# Battlebot_Main.net
KiCad netlist of a schematic drawn in Altium Designer
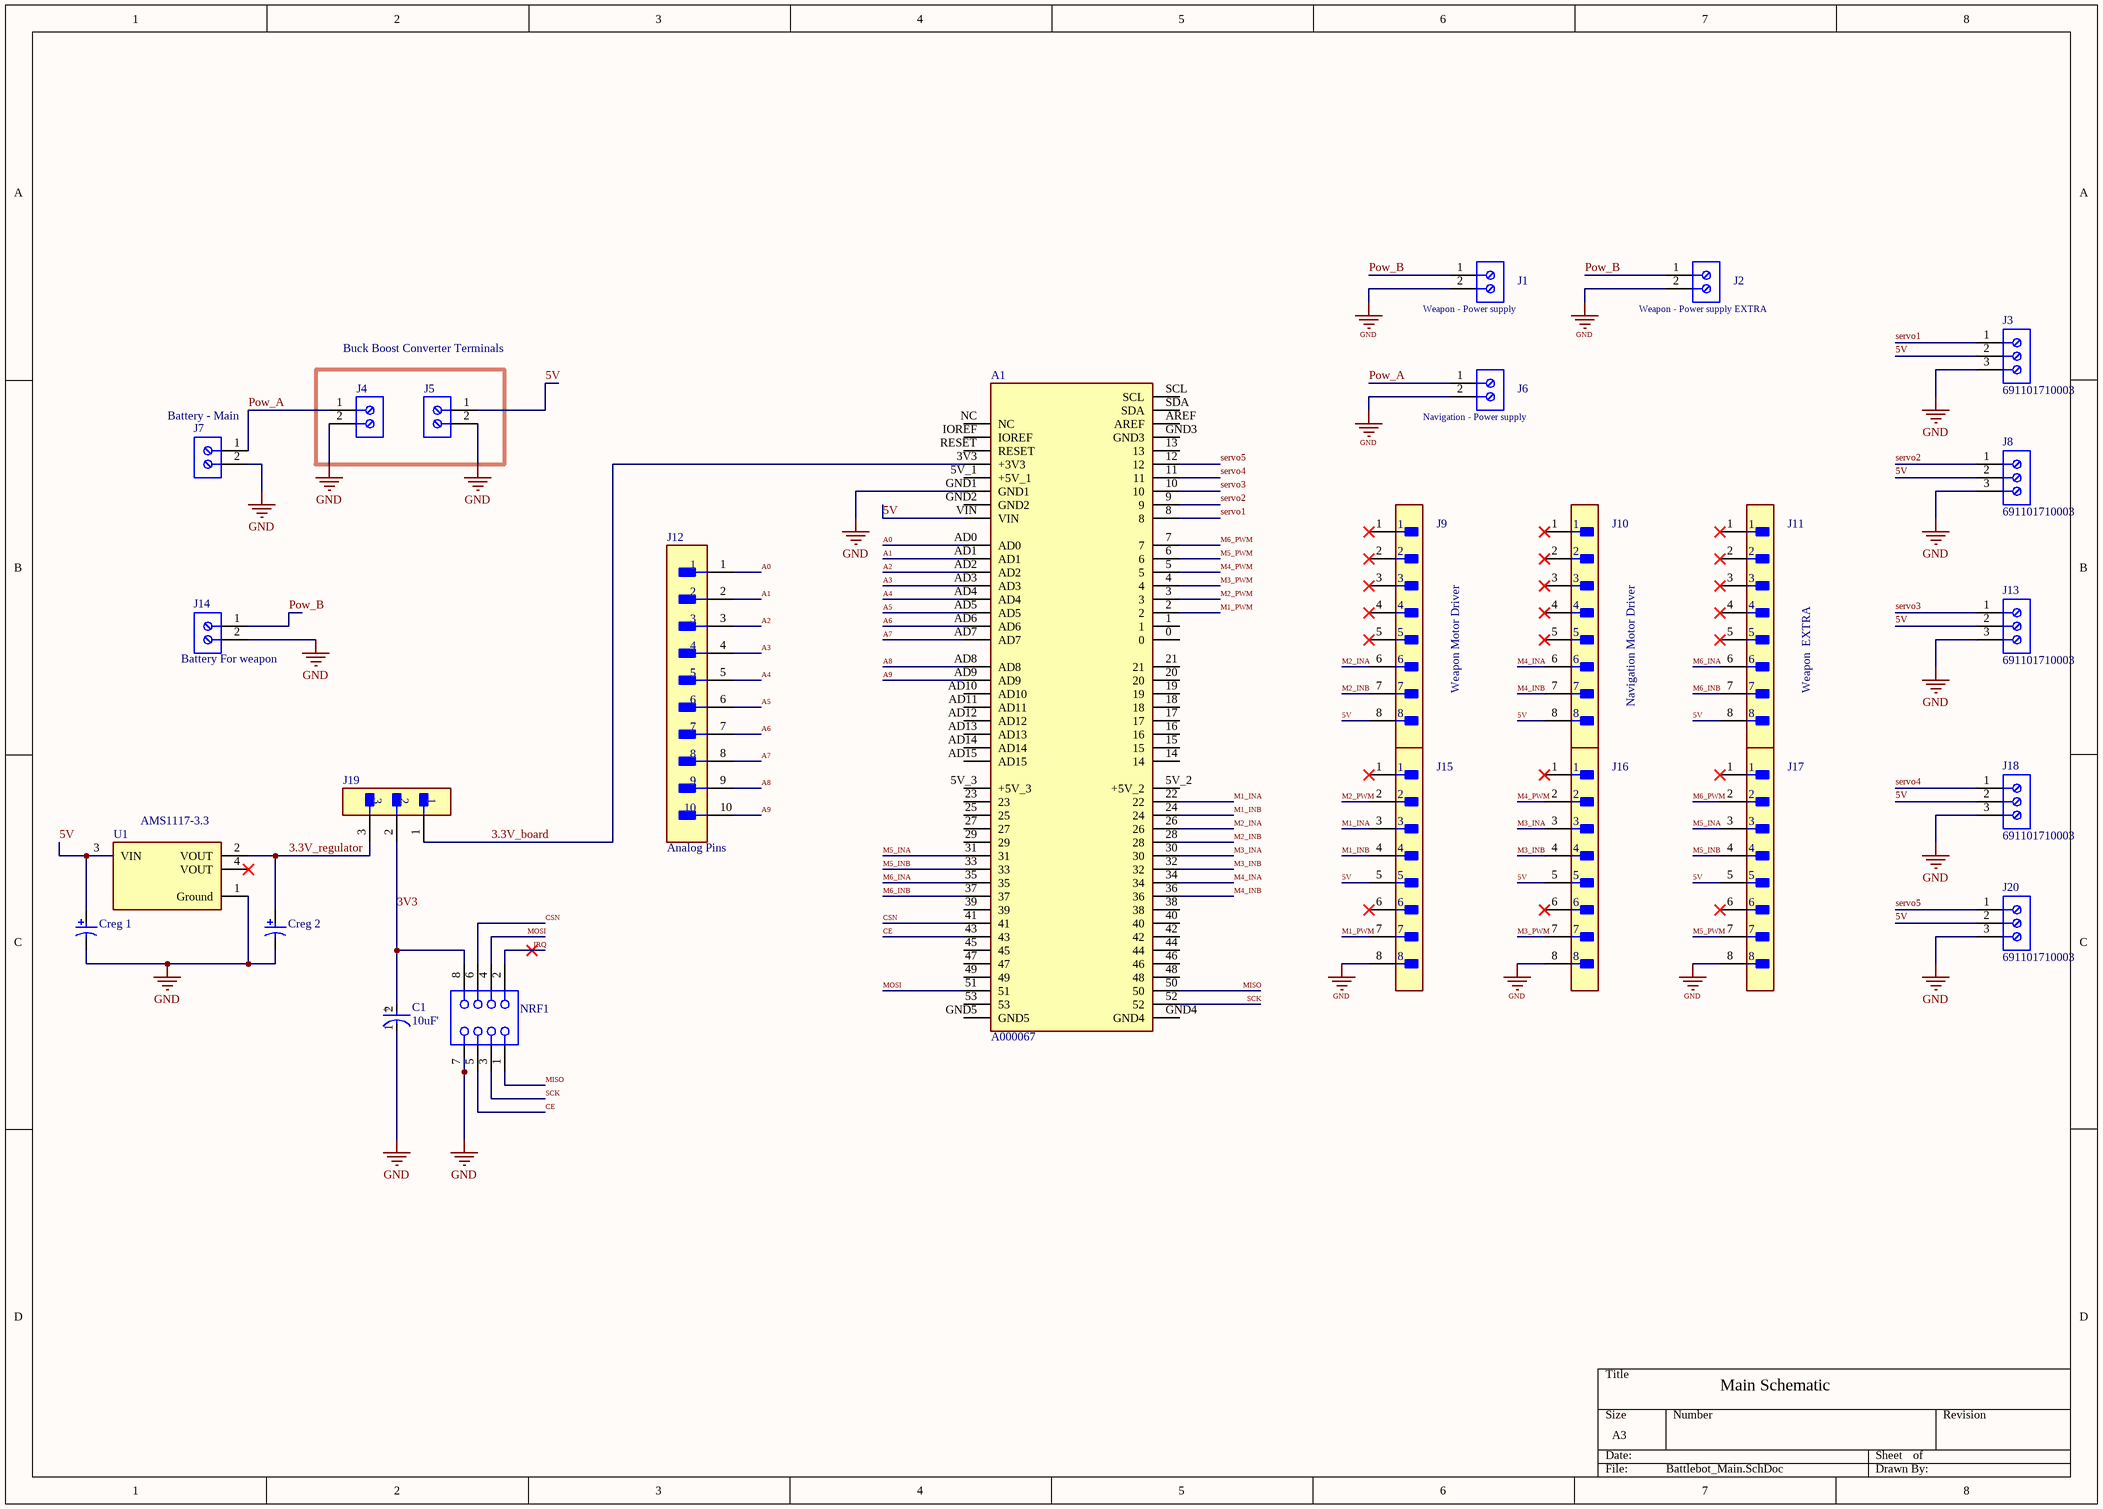
[diagram p0: Battlebot_Main.SchDoc]

(export (version "E")
  (design (tool "Eeschema 10.0.6"))
  (components
    (comp (ref "A1")
      (value "A000067")
      (footprint "ARDUINO_A000067")
      (fields (field (name "MF") "Arduino"))
      (libsource (lib "Schlib1") (part "A000067"))
    )
    (comp (ref "C1")
      (value "10uF'")
      (footprint "FP-RAD-TH-D_5_0_5-L_11_1-MFG")
      (description "Aluminum Electrolytic Capacitors (Radial Lead Type) AEC-Q200 Qualified 47uF ±20% 35V")
      (fields (field (name "VOLTAGE") "35V") (field (name "TOLERANCE") "20%"))
      (libsource (lib "Altium Content Vault") (part "a00bbbee19879c290e62620ae7e47b1"))
    )
    (comp (ref "Creg 1")
      (value "ECA1HM100")
      (footprint "CAPPR55-200-1100X500X1200")
      (description "Aluminum Electrolytic Capacitor, 10 uF, +/- 20%, 50 V, -40 to 85 degC, 2-Pin THD, RoHS, Bulk")
      (fields (field (name "MANUFACTURER") "Panasonic") (field (name "TOLERANCE") "20%"))
      (libsource (lib "Altium Content Vault") (part "CAP-P-2"))
    )
    (comp (ref "Creg 2")
      (value "ECA1HM100")
      (footprint "CAPPR55-200-1100X500X1200")
      (description "Aluminum Electrolytic Capacitor, 10 uF, +/- 20%, 50 V, -40 to 85 degC, 2-Pin THD, RoHS, Bulk")
      (fields (field (name "MANUFACTURER") "Panasonic") (field (name "TOLERANCE") "20%"))
      (libsource (lib "Altium Content Vault") (part "CAP-P-2"))
    )
    (comp (ref "J1")
      (value "Weapon - Power supply")
      (footprint "691213710002")
      (description "Serie 213 - 5.00 mm Horizontal Entry Modular with RisingCage Clamp WR-TBL, 2 pin")
      (fields
        (field (name "MANUFACTURER") "Wurth Elektronik")
        (field (name "PART NUMBER") "691213710002")
        (field (name "PUBLISHER") "WurthElektronik")
      )
      (libsource (lib "Altium Content Vault") (part "WE-CN-1P-F-TB2"))
    )
    (comp (ref "J2")
      (value "Weapon - Power supply EXTRA")
      (footprint "691213710002")
      (description "Serie 213 - 5.00 mm Horizontal Entry Modular with RisingCage Clamp WR-TBL, 2 pin")
      (fields
        (field (name "MANUFACTURER") "Wurth Elektronik")
        (field (name "PART NUMBER") "691213710002")
        (field (name "PUBLISHER") "WurthElektronik")
      )
      (libsource (lib "Altium Content Vault") (part "WE-CN-1P-F-TB2"))
    )
    (comp (ref "J3")
      (value "691101710003")
      (footprint "691101710003")
      (fields (field (name "VOLTAGE") "250V"))
      (libsource (lib "Altium Content Vault") (part "TBL - 1R - 03P - Screw"))
    )
    (comp (ref "J4")
      (value "691213710002")
      (footprint "691213710002")
      (description "Serie 213 - 5.00 mm Horizontal Entry Modular with RisingCage Clamp WR-TBL, 2 pin")
      (fields (field (name "MANUFACTURER") "Wurth Elektronik") (field (name "PUBLISHER") "WurthElektronik"))
      (libsource (lib "Altium Content Vault") (part "WE-CN-1P-F-TB2"))
    )
    (comp (ref "J5")
      (value "691213710002")
      (footprint "691213710002")
      (description "Serie 213 - 5.00 mm Horizontal Entry Modular with RisingCage Clamp WR-TBL, 2 pin")
      (fields (field (name "MANUFACTURER") "Wurth Elektronik") (field (name "PUBLISHER") "WurthElektronik"))
      (libsource (lib "Altium Content Vault") (part "WE-CN-1P-F-TB2"))
    )
    (comp (ref "J6")
      (value "Navigation - Power supply")
      (footprint "691213710002")
      (description "Serie 213 - 5.00 mm Horizontal Entry Modular with RisingCage Clamp WR-TBL, 2 pin")
      (fields
        (field (name "MANUFACTURER") "Wurth Elektronik")
        (field (name "PART NUMBER") "691213710002")
        (field (name "PUBLISHER") "WurthElektronik")
      )
      (libsource (lib "Altium Content Vault") (part "WE-CN-1P-F-TB2"))
    )
    (comp (ref "J7")
      (value "691213710002")
      (footprint "691213710002")
      (description "Serie 213 - 5.00 mm Horizontal Entry Modular with RisingCage Clamp WR-TBL, 2 pin")
      (fields (field (name "MANUFACTURER") "Wurth Elektronik") (field (name "PUBLISHER") "WurthElektronik"))
      (libsource (lib "Altium Content Vault") (part "WE-CN-1P-F-TB2"))
    )
    (comp (ref "J8")
      (value "691101710003")
      (footprint "691101710003")
      (fields (field (name "VOLTAGE") "250V"))
      (libsource (lib "Altium Content Vault") (part "TBL - 1R - 03P - Screw"))
    )
    (comp (ref "J9")
      (value "PREC008SAAN-RC")
      (footprint "FP-PREC008SAAN-RC-MFG")
      (description "CONN HEADER VERT 8POS 2.54MM")
      (fields
        (field (name "MANUFACTURER") "Sullins")
        (field (name "OCTOPART") "https://octopart.com/prec008saan-rc-sullins-22265145")
      )
      (libsource (lib "Altium Content Vault") (part "99ec2b232beb5d2356d4d77f6a047f0"))
    )
    (comp (ref "J10")
      (value "PREC008SAAN-RC")
      (footprint "FP-PREC008SAAN-RC-MFG")
      (description "CONN HEADER VERT 8POS 2.54MM")
      (fields
        (field (name "MANUFACTURER") "Sullins")
        (field (name "OCTOPART") "https://octopart.com/prec008saan-rc-sullins-22265145")
      )
      (libsource (lib "Altium Content Vault") (part "99ec2b232beb5d2356d4d77f6a047f0"))
    )
    (comp (ref "J11")
      (value "PREC008SAAN-RC")
      (footprint "FP-PREC008SAAN-RC-MFG")
      (description "CONN HEADER VERT 8POS 2.54MM")
      (fields
        (field (name "MANUFACTURER") "Sullins")
        (field (name "OCTOPART") "https://octopart.com/prec008saan-rc-sullins-22265145")
      )
      (libsource (lib "Altium Content Vault") (part "99ec2b232beb5d2356d4d77f6a047f0"))
    )
    (comp (ref "J12")
      (value "Analog Pins")
      (footprint "FP-4-644456-0-MFG")
      (description "CONN HEADER VERT 10POS 2.54MM")
      (fields
        (field (name "OCTOPART") "https://octopart.com/4-644456-0-te+connectivity-39514173")
        (field (name "MANUFACTURER PART NUMBER") "4-644456-0")
      )
      (libsource (lib "Altium Content Vault") (part "aee40dc8b284c03a16094555aa210be"))
    )
    (comp (ref "J13")
      (value "691101710003")
      (footprint "691101710003")
      (fields (field (name "VOLTAGE") "250V"))
      (libsource (lib "Altium Content Vault") (part "TBL - 1R - 03P - Screw"))
    )
    (comp (ref "J14")
      (value "691213710002")
      (footprint "691213710002")
      (description "Serie 213 - 5.00 mm Horizontal Entry Modular with RisingCage Clamp WR-TBL, 2 pin")
      (fields (field (name "MANUFACTURER") "Wurth Elektronik") (field (name "PUBLISHER") "WurthElektronik"))
      (libsource (lib "Altium Content Vault") (part "WE-CN-1P-F-TB2"))
    )
    (comp (ref "J15")
      (value "PREC008SAAN-RC")
      (footprint "FP-PREC008SAAN-RC-MFG")
      (description "CONN HEADER VERT 8POS 2.54MM")
      (fields
        (field (name "MANUFACTURER") "Sullins")
        (field (name "OCTOPART") "https://octopart.com/prec008saan-rc-sullins-22265145")
      )
      (libsource (lib "Altium Content Vault") (part "99ec2b232beb5d2356d4d77f6a047f0"))
    )
    (comp (ref "J16")
      (value "PREC008SAAN-RC")
      (footprint "FP-PREC008SAAN-RC-MFG")
      (description "CONN HEADER VERT 8POS 2.54MM")
      (fields
        (field (name "MANUFACTURER") "Sullins")
        (field (name "OCTOPART") "https://octopart.com/prec008saan-rc-sullins-22265145")
      )
      (libsource (lib "Altium Content Vault") (part "99ec2b232beb5d2356d4d77f6a047f0"))
    )
    (comp (ref "J17")
      (value "PREC008SAAN-RC")
      (footprint "FP-PREC008SAAN-RC-MFG")
      (description "CONN HEADER VERT 8POS 2.54MM")
      (fields
        (field (name "MANUFACTURER") "Sullins")
        (field (name "OCTOPART") "https://octopart.com/prec008saan-rc-sullins-22265145")
      )
      (libsource (lib "Altium Content Vault") (part "99ec2b232beb5d2356d4d77f6a047f0"))
    )
    (comp (ref "J18")
      (value "691101710003")
      (footprint "691101710003")
      (fields (field (name "VOLTAGE") "250V"))
      (libsource (lib "Altium Content Vault") (part "TBL - 1R - 03P - Screw"))
    )
    (comp (ref "J19")
      (value "22-28-4030")
      (footprint "FP-22-28-4030-MFG")
      (description "CONN HEADER VERT 3POS 2.54MM")
      (fields
        (field (name "OCTOPART") "https://octopart.com/0022284030-molex-10476094")
        (field (name "MANUFACTURER") "Molex")
      )
      (libsource (lib "Altium Content Vault") (part "0d3f023dd272f625e17a2be33dea85f"))
    )
    (comp (ref "J20")
      (value "691101710003")
      (footprint "691101710003")
      (fields (field (name "VOLTAGE") "250V"))
      (libsource (lib "Altium Content Vault") (part "TBL - 1R - 03P - Screw"))
    )
    (comp (ref "NRF1")
      (value "SSW-104-02-G-D")
      (footprint "SMTC-SSW-104-02-X-D")
      (description "SQ Post Socket, Through-hole, Vertical, -55 to 125 degC, 2.54mm Pitch, 8-Pin, Female, RoHS")
      (fields (field (name "MANUFACTURER") "Samtec"))
      (libsource (lib "Altium Content Vault") (part "SMTC-SSW-104-X-X-D"))
    )
    (comp (ref "U1")
      (value "AMS1117-3.3")
      (footprint "FP-AMS1117-IPC_C")
      (description "LDO Voltage Regulators 1A, 3.3V")
      (fields
        (field (name "OCTOPART") "https://octopart.com/ams1117-3.3-advanced+monolithic+systems-25899300")
        (field (name "MANUFACTURER") "Advanced Monolithic Systems")
      )
      (libsource (lib "Altium Content Vault") (part "8bdbb5f8e77002000e30dd2845d0354"))
    )
  )
  (nets
    (net (code "1") (name "/3.3V_board") (class "Default")
      (node (ref "A1") (pin "3V3") (pinfunction "+3V3_3V3") (pintype "passive"))
      (node (ref "J19") (pin "1") (pinfunction "1_1") (pintype "passive"))
    )
    (net (code "2") (name "/3.3V_regulator") (class "Default")
      (node (ref "Creg 2") (pin "1") (pinfunction "1_1") (pintype "passive"))
      (node (ref "J19") (pin "3") (pinfunction "3_3") (pintype "passive"))
      (node (ref "U1") (pin "2") (pinfunction "VOUT_2") (pintype "passive"))
    )
    (net (code "3") (name "/3V3") (class "Default")
      (node (ref "C1") (pin "2") (pinfunction "A_2") (pintype "passive"))
      (node (ref "J19") (pin "2") (pinfunction "2_2") (pintype "passive"))
      (node (ref "NRF1") (pin "8") (pinfunction "8_8") (pintype "passive"))
    )
    (net (code "4") (name "/5V") (class "Default")
      (node (ref "A1") (pin "VIN") (pinfunction "VIN_VIN") (pintype "passive"))
      (node (ref "Creg 1") (pin "1") (pinfunction "1_1") (pintype "passive"))
      (node (ref "J10") (pin "8") (pinfunction "8_8") (pintype "passive"))
      (node (ref "J11") (pin "8") (pinfunction "8_8") (pintype "passive"))
      (node (ref "J13") (pin "2") (pinfunction "2_2") (pintype "passive"))
      (node (ref "J15") (pin "5") (pinfunction "5_5") (pintype "passive"))
      (node (ref "J16") (pin "5") (pinfunction "5_5") (pintype "passive"))
      (node (ref "J17") (pin "5") (pinfunction "5_5") (pintype "passive"))
      (node (ref "J18") (pin "2") (pinfunction "2_2") (pintype "passive"))
      (node (ref "J20") (pin "2") (pinfunction "2_2") (pintype "passive"))
      (node (ref "J3") (pin "2") (pinfunction "2_2") (pintype "passive"))
      (node (ref "J5") (pin "1") (pinfunction "1_1") (pintype "passive"))
      (node (ref "J8") (pin "2") (pinfunction "2_2") (pintype "passive"))
      (node (ref "J9") (pin "8") (pinfunction "8_8") (pintype "passive"))
      (node (ref "U1") (pin "3") (pinfunction "VIN_3") (pintype "power_in"))
    )
    (net (code "5") (name "/A0") (class "Default")
      (node (ref "A1") (pin "AD0") (pinfunction "AD0_AD0") (pintype "passive"))
      (node (ref "J12") (pin "1") (pinfunction "1_1") (pintype "passive"))
    )
    (net (code "6") (name "/A1") (class "Default")
      (node (ref "A1") (pin "AD1") (pinfunction "AD1_AD1") (pintype "passive"))
      (node (ref "J12") (pin "2") (pinfunction "2_2") (pintype "passive"))
    )
    (net (code "7") (name "/A2") (class "Default")
      (node (ref "A1") (pin "AD2") (pinfunction "AD2_AD2") (pintype "passive"))
      (node (ref "J12") (pin "3") (pinfunction "3_3") (pintype "passive"))
    )
    (net (code "8") (name "/A3") (class "Default")
      (node (ref "A1") (pin "AD3") (pinfunction "AD3_AD3") (pintype "passive"))
      (node (ref "J12") (pin "4") (pinfunction "4_4") (pintype "passive"))
    )
    (net (code "9") (name "/A4") (class "Default")
      (node (ref "A1") (pin "AD4") (pinfunction "AD4_AD4") (pintype "passive"))
      (node (ref "J12") (pin "5") (pinfunction "5_5") (pintype "passive"))
    )
    (net (code "10") (name "/A5") (class "Default")
      (node (ref "A1") (pin "AD5") (pinfunction "AD5_AD5") (pintype "passive"))
      (node (ref "J12") (pin "6") (pinfunction "6_6") (pintype "passive"))
    )
    (net (code "11") (name "/A6") (class "Default")
      (node (ref "A1") (pin "AD6") (pinfunction "AD6_AD6") (pintype "passive"))
      (node (ref "J12") (pin "7") (pinfunction "7_7") (pintype "passive"))
    )
    (net (code "12") (name "/A7") (class "Default")
      (node (ref "A1") (pin "AD7") (pinfunction "AD7_AD7") (pintype "passive"))
      (node (ref "J12") (pin "8") (pinfunction "8_8") (pintype "passive"))
    )
    (net (code "13") (name "/A8") (class "Default")
      (node (ref "A1") (pin "AD8") (pinfunction "AD8_AD8") (pintype "passive"))
      (node (ref "J12") (pin "9") (pinfunction "9_9") (pintype "passive"))
    )
    (net (code "14") (name "/A9") (class "Default")
      (node (ref "A1") (pin "AD9") (pinfunction "AD9_AD9") (pintype "passive"))
      (node (ref "J12") (pin "10") (pinfunction "10_10") (pintype "passive"))
    )
    (net (code "15") (name "/CE") (class "Default")
      (node (ref "A1") (pin "43") (pinfunction "43_43") (pintype "passive"))
      (node (ref "NRF1") (pin "5") (pinfunction "5_5") (pintype "passive"))
    )
    (net (code "16") (name "/CSN") (class "Default")
      (node (ref "A1") (pin "41") (pinfunction "41_41") (pintype "passive"))
      (node (ref "NRF1") (pin "6") (pinfunction "6_6") (pintype "passive"))
    )
    (net (code "17") (name "/IRQ") (class "Default")
      (node (ref "NRF1") (pin "2") (pinfunction "2_2") (pintype "passive"))
    )
    (net (code "18") (name "/M1_INA") (class "Default")
      (node (ref "A1") (pin "22") (pinfunction "22_22") (pintype "passive"))
      (node (ref "J15") (pin "3") (pinfunction "3_3") (pintype "passive"))
    )
    (net (code "19") (name "/M1_INB") (class "Default")
      (node (ref "A1") (pin "24") (pinfunction "24_24") (pintype "passive"))
      (node (ref "J15") (pin "4") (pinfunction "4_4") (pintype "passive"))
    )
    (net (code "20") (name "/M1_PWM") (class "Default")
      (node (ref "A1") (pin "2") (pinfunction "2_2") (pintype "passive"))
      (node (ref "J15") (pin "7") (pinfunction "7_7") (pintype "passive"))
    )
    (net (code "21") (name "/M2_INA") (class "Default")
      (node (ref "A1") (pin "26") (pinfunction "26_26") (pintype "passive"))
      (node (ref "J9") (pin "6") (pinfunction "6_6") (pintype "passive"))
    )
    (net (code "22") (name "/M2_INB") (class "Default")
      (node (ref "A1") (pin "28") (pinfunction "28_28") (pintype "passive"))
      (node (ref "J9") (pin "7") (pinfunction "7_7") (pintype "passive"))
    )
    (net (code "23") (name "/M2_PWM") (class "Default")
      (node (ref "A1") (pin "3") (pinfunction "3_3") (pintype "passive"))
      (node (ref "J15") (pin "2") (pinfunction "2_2") (pintype "passive"))
    )
    (net (code "24") (name "/M3_INA") (class "Default")
      (node (ref "A1") (pin "30") (pinfunction "30_30") (pintype "passive"))
      (node (ref "J16") (pin "3") (pinfunction "3_3") (pintype "passive"))
    )
    (net (code "25") (name "/M3_INB") (class "Default")
      (node (ref "A1") (pin "32") (pinfunction "32_32") (pintype "passive"))
      (node (ref "J16") (pin "4") (pinfunction "4_4") (pintype "passive"))
    )
    (net (code "26") (name "/M3_PWM") (class "Default")
      (node (ref "A1") (pin "4") (pinfunction "4_4") (pintype "passive"))
      (node (ref "J16") (pin "7") (pinfunction "7_7") (pintype "passive"))
    )
    (net (code "27") (name "/M4_INA") (class "Default")
      (node (ref "A1") (pin "34") (pinfunction "34_34") (pintype "passive"))
      (node (ref "J10") (pin "6") (pinfunction "6_6") (pintype "passive"))
    )
    (net (code "28") (name "/M4_INB") (class "Default")
      (node (ref "A1") (pin "36") (pinfunction "36_36") (pintype "passive"))
      (node (ref "J10") (pin "7") (pinfunction "7_7") (pintype "passive"))
    )
    (net (code "29") (name "/M4_PWM") (class "Default")
      (node (ref "A1") (pin "5") (pinfunction "5_5") (pintype "passive"))
      (node (ref "J16") (pin "2") (pinfunction "2_2") (pintype "passive"))
    )
    (net (code "30") (name "/M5_INA") (class "Default")
      (node (ref "A1") (pin "31") (pinfunction "31_31") (pintype "passive"))
      (node (ref "J17") (pin "3") (pinfunction "3_3") (pintype "passive"))
    )
    (net (code "31") (name "/M5_INB") (class "Default")
      (node (ref "A1") (pin "33") (pinfunction "33_33") (pintype "passive"))
      (node (ref "J17") (pin "4") (pinfunction "4_4") (pintype "passive"))
    )
    (net (code "32") (name "/M5_PWM") (class "Default")
      (node (ref "A1") (pin "6") (pinfunction "6_6") (pintype "passive"))
      (node (ref "J17") (pin "7") (pinfunction "7_7") (pintype "passive"))
    )
    (net (code "33") (name "/M6_INA") (class "Default")
      (node (ref "A1") (pin "35") (pinfunction "35_35") (pintype "passive"))
      (node (ref "J11") (pin "6") (pinfunction "6_6") (pintype "passive"))
    )
    (net (code "34") (name "/M6_INB") (class "Default")
      (node (ref "A1") (pin "37") (pinfunction "37_37") (pintype "passive"))
      (node (ref "J11") (pin "7") (pinfunction "7_7") (pintype "passive"))
    )
    (net (code "35") (name "/M6_PWM") (class "Default")
      (node (ref "A1") (pin "7") (pinfunction "7_7") (pintype "passive"))
      (node (ref "J17") (pin "2") (pinfunction "2_2") (pintype "passive"))
    )
    (net (code "36") (name "/MISO") (class "Default")
      (node (ref "A1") (pin "50") (pinfunction "50_50") (pintype "passive"))
      (node (ref "NRF1") (pin "1") (pinfunction "1_1") (pintype "passive"))
    )
    (net (code "37") (name "/MOSI") (class "Default")
      (node (ref "A1") (pin "51") (pinfunction "51_51") (pintype "passive"))
      (node (ref "NRF1") (pin "4") (pinfunction "4_4") (pintype "passive"))
    )
    (net (code "38") (name "/Pow_A") (class "Default")
      (node (ref "J4") (pin "1") (pinfunction "1_1") (pintype "passive"))
      (node (ref "J6") (pin "1") (pinfunction "1_1") (pintype "passive"))
      (node (ref "J7") (pin "1") (pinfunction "1_1") (pintype "passive"))
    )
    (net (code "39") (name "/Pow_B") (class "Default")
      (node (ref "J1") (pin "1") (pinfunction "1_1") (pintype "passive"))
      (node (ref "J14") (pin "1") (pinfunction "1_1") (pintype "passive"))
      (node (ref "J2") (pin "1") (pinfunction "1_1") (pintype "passive"))
    )
    (net (code "40") (name "/SCK") (class "Default")
      (node (ref "A1") (pin "52") (pinfunction "52_52") (pintype "passive"))
      (node (ref "NRF1") (pin "3") (pinfunction "3_3") (pintype "passive"))
    )
    (net (code "41") (name "/servo1") (class "Default")
      (node (ref "A1") (pin "8") (pinfunction "8_8") (pintype "passive"))
      (node (ref "J3") (pin "1") (pinfunction "1_1") (pintype "passive"))
    )
    (net (code "42") (name "/servo2") (class "Default")
      (node (ref "A1") (pin "9") (pinfunction "9_9") (pintype "passive"))
      (node (ref "J8") (pin "1") (pinfunction "1_1") (pintype "passive"))
    )
    (net (code "43") (name "/servo3") (class "Default")
      (node (ref "A1") (pin "10") (pinfunction "10_10") (pintype "passive"))
      (node (ref "J13") (pin "1") (pinfunction "1_1") (pintype "passive"))
    )
    (net (code "44") (name "/servo4") (class "Default")
      (node (ref "A1") (pin "11") (pinfunction "11_11") (pintype "passive"))
      (node (ref "J18") (pin "1") (pinfunction "1_1") (pintype "passive"))
    )
    (net (code "45") (name "/servo5") (class "Default")
      (node (ref "A1") (pin "12") (pinfunction "12_12") (pintype "passive"))
      (node (ref "J20") (pin "1") (pinfunction "1_1") (pintype "passive"))
    )
    (net (code "46") (name "GND") (class "Default")
      (node (ref "A1") (pin "GND1") (pinfunction "GND1_GND1") (pintype "passive"))
      (node (ref "C1") (pin "1") (pinfunction "C_1") (pintype "passive"))
      (node (ref "Creg 1") (pin "2") (pinfunction "2_2") (pintype "passive"))
      (node (ref "Creg 2") (pin "2") (pinfunction "2_2") (pintype "passive"))
      (node (ref "J1") (pin "2") (pinfunction "2_2") (pintype "passive"))
      (node (ref "J13") (pin "3") (pinfunction "3_3") (pintype "passive"))
      (node (ref "J14") (pin "2") (pinfunction "2_2") (pintype "passive"))
      (node (ref "J15") (pin "8") (pinfunction "8_8") (pintype "passive"))
      (node (ref "J16") (pin "8") (pinfunction "8_8") (pintype "passive"))
      (node (ref "J17") (pin "8") (pinfunction "8_8") (pintype "passive"))
      (node (ref "J18") (pin "3") (pinfunction "3_3") (pintype "passive"))
      (node (ref "J2") (pin "2") (pinfunction "2_2") (pintype "passive"))
      (node (ref "J20") (pin "3") (pinfunction "3_3") (pintype "passive"))
      (node (ref "J3") (pin "3") (pinfunction "3_3") (pintype "passive"))
      (node (ref "J4") (pin "2") (pinfunction "2_2") (pintype "passive"))
      (node (ref "J5") (pin "2") (pinfunction "2_2") (pintype "passive"))
      (node (ref "J6") (pin "2") (pinfunction "2_2") (pintype "passive"))
      (node (ref "J7") (pin "2") (pinfunction "2_2") (pintype "passive"))
      (node (ref "J8") (pin "3") (pinfunction "3_3") (pintype "passive"))
      (node (ref "NRF1") (pin "7") (pinfunction "7_7") (pintype "passive"))
      (node (ref "U1") (pin "1") (pinfunction "Ground_1") (pintype "power_in"))
    )
    (net (code "47") (name "unconnected-(A1-+5V_1-Pad5V_1)") (class "Default")
      (node (ref "A1") (pin "5V_1") (pinfunction "+5V_1_5V_1") (pintype "passive"))
    )
    (net (code "48") (name "unconnected-(A1-+5V_2-Pad5V_2)") (class "Default")
      (node (ref "A1") (pin "5V_2") (pinfunction "+5V_2_5V_2") (pintype "passive"))
    )
    (net (code "49") (name "unconnected-(A1-+5V_3-Pad5V_3)") (class "Default")
      (node (ref "A1") (pin "5V_3") (pinfunction "+5V_3_5V_3") (pintype "passive"))
    )
    (net (code "50") (name "unconnected-(A1-Pad0)") (class "Default")
      (node (ref "A1") (pin "0") (pinfunction "0_0") (pintype "passive"))
    )
    (net (code "51") (name "unconnected-(A1-Pad1)") (class "Default")
      (node (ref "A1") (pin "1") (pinfunction "1_1") (pintype "passive"))
    )
    (net (code "52") (name "unconnected-(A1-Pad13)") (class "Default")
      (node (ref "A1") (pin "13") (pinfunction "13_13") (pintype "passive"))
    )
    (net (code "53") (name "unconnected-(A1-Pad14)") (class "Default")
      (node (ref "A1") (pin "14") (pinfunction "14_14") (pintype "passive"))
    )
    (net (code "54") (name "unconnected-(A1-Pad15)") (class "Default")
      (node (ref "A1") (pin "15") (pinfunction "15_15") (pintype "passive"))
    )
    (net (code "55") (name "unconnected-(A1-Pad16)") (class "Default")
      (node (ref "A1") (pin "16") (pinfunction "16_16") (pintype "passive"))
    )
    (net (code "56") (name "unconnected-(A1-Pad17)") (class "Default")
      (node (ref "A1") (pin "17") (pinfunction "17_17") (pintype "passive"))
    )
    (net (code "57") (name "unconnected-(A1-Pad18)") (class "Default")
      (node (ref "A1") (pin "18") (pinfunction "18_18") (pintype "passive"))
    )
    (net (code "58") (name "unconnected-(A1-Pad19)") (class "Default")
      (node (ref "A1") (pin "19") (pinfunction "19_19") (pintype "passive"))
    )
    (net (code "59") (name "unconnected-(A1-Pad20)") (class "Default")
      (node (ref "A1") (pin "20") (pinfunction "20_20") (pintype "passive"))
    )
    (net (code "60") (name "unconnected-(A1-Pad21)") (class "Default")
      (node (ref "A1") (pin "21") (pinfunction "21_21") (pintype "passive"))
    )
    (net (code "61") (name "unconnected-(A1-Pad23)") (class "Default")
      (node (ref "A1") (pin "23") (pinfunction "23_23") (pintype "passive"))
    )
    (net (code "62") (name "unconnected-(A1-Pad25)") (class "Default")
      (node (ref "A1") (pin "25") (pinfunction "25_25") (pintype "passive"))
    )
    (net (code "63") (name "unconnected-(A1-Pad27)") (class "Default")
      (node (ref "A1") (pin "27") (pinfunction "27_27") (pintype "passive"))
    )
    (net (code "64") (name "unconnected-(A1-Pad29)") (class "Default")
      (node (ref "A1") (pin "29") (pinfunction "29_29") (pintype "passive"))
    )
    (net (code "65") (name "unconnected-(A1-Pad38)") (class "Default")
      (node (ref "A1") (pin "38") (pinfunction "38_38") (pintype "passive"))
    )
    (net (code "66") (name "unconnected-(A1-Pad39)") (class "Default")
      (node (ref "A1") (pin "39") (pinfunction "39_39") (pintype "passive"))
    )
    (net (code "67") (name "unconnected-(A1-Pad40)") (class "Default")
      (node (ref "A1") (pin "40") (pinfunction "40_40") (pintype "passive"))
    )
    (net (code "68") (name "unconnected-(A1-Pad42)") (class "Default")
      (node (ref "A1") (pin "42") (pinfunction "42_42") (pintype "passive"))
    )
    (net (code "69") (name "unconnected-(A1-Pad44)") (class "Default")
      (node (ref "A1") (pin "44") (pinfunction "44_44") (pintype "passive"))
    )
    (net (code "70") (name "unconnected-(A1-Pad45)") (class "Default")
      (node (ref "A1") (pin "45") (pinfunction "45_45") (pintype "passive"))
    )
    (net (code "71") (name "unconnected-(A1-Pad46)") (class "Default")
      (node (ref "A1") (pin "46") (pinfunction "46_46") (pintype "passive"))
    )
    (net (code "72") (name "unconnected-(A1-Pad47)") (class "Default")
      (node (ref "A1") (pin "47") (pinfunction "47_47") (pintype "passive"))
    )
    (net (code "73") (name "unconnected-(A1-Pad48)") (class "Default")
      (node (ref "A1") (pin "48") (pinfunction "48_48") (pintype "passive"))
    )
    (net (code "74") (name "unconnected-(A1-Pad49)") (class "Default")
      (node (ref "A1") (pin "49") (pinfunction "49_49") (pintype "passive"))
    )
    (net (code "75") (name "unconnected-(A1-Pad53)") (class "Default")
      (node (ref "A1") (pin "53") (pinfunction "53_53") (pintype "passive"))
    )
    (net (code "76") (name "unconnected-(A1-PadAD10)") (class "Default")
      (node (ref "A1") (pin "AD10") (pinfunction "AD10_AD10") (pintype "passive"))
    )
    (net (code "77") (name "unconnected-(A1-PadAD11)") (class "Default")
      (node (ref "A1") (pin "AD11") (pinfunction "AD11_AD11") (pintype "passive"))
    )
    (net (code "78") (name "unconnected-(A1-PadAD12)") (class "Default")
      (node (ref "A1") (pin "AD12") (pinfunction "AD12_AD12") (pintype "passive"))
    )
    (net (code "79") (name "unconnected-(A1-PadAD13)") (class "Default")
      (node (ref "A1") (pin "AD13") (pinfunction "AD13_AD13") (pintype "passive"))
    )
    (net (code "80") (name "unconnected-(A1-PadAD14)") (class "Default")
      (node (ref "A1") (pin "AD14") (pinfunction "AD14_AD14") (pintype "passive"))
    )
    (net (code "81") (name "unconnected-(A1-PadAD15)") (class "Default")
      (node (ref "A1") (pin "AD15") (pinfunction "AD15_AD15") (pintype "passive"))
    )
    (net (code "82") (name "unconnected-(A1-PadAREF)") (class "Default")
      (node (ref "A1") (pin "AREF") (pinfunction "AREF_AREF") (pintype "passive"))
    )
    (net (code "83") (name "unconnected-(A1-PadGND2)") (class "Default")
      (node (ref "A1") (pin "GND2") (pinfunction "GND2_GND2") (pintype "passive"))
    )
    (net (code "84") (name "unconnected-(A1-PadGND3)") (class "Default")
      (node (ref "A1") (pin "GND3") (pinfunction "GND3_GND3") (pintype "passive"))
    )
    (net (code "85") (name "unconnected-(A1-PadGND4)") (class "Default")
      (node (ref "A1") (pin "GND4") (pinfunction "GND4_GND4") (pintype "passive"))
    )
    (net (code "86") (name "unconnected-(A1-PadGND5)") (class "Default")
      (node (ref "A1") (pin "GND5") (pinfunction "GND5_GND5") (pintype "passive"))
    )
    (net (code "87") (name "unconnected-(A1-PadIOREF)") (class "Default")
      (node (ref "A1") (pin "IOREF") (pinfunction "IOREF_IOREF") (pintype "passive"))
    )
    (net (code "88") (name "unconnected-(A1-PadNC)") (class "Default")
      (node (ref "A1") (pin "NC") (pinfunction "NC_NC") (pintype "passive"))
    )
    (net (code "89") (name "unconnected-(A1-PadRESET)") (class "Default")
      (node (ref "A1") (pin "RESET") (pinfunction "RESET_RESET") (pintype "passive"))
    )
    (net (code "90") (name "unconnected-(A1-PadSCL)") (class "Default")
      (node (ref "A1") (pin "SCL") (pinfunction "SCL_SCL") (pintype "passive"))
    )
    (net (code "91") (name "unconnected-(A1-PadSDA)") (class "Default")
      (node (ref "A1") (pin "SDA") (pinfunction "SDA_SDA") (pintype "passive"))
    )
    (net (code "92") (name "unconnected-(J9-Pad1)") (class "Default")
      (node (ref "J9") (pin "1") (pinfunction "1_1") (pintype "passive+no_connect"))
    )
    (net (code "93") (name "unconnected-(J9-Pad2)") (class "Default")
      (node (ref "J9") (pin "2") (pinfunction "2_2") (pintype "passive+no_connect"))
    )
    (net (code "94") (name "unconnected-(J9-Pad3)") (class "Default")
      (node (ref "J9") (pin "3") (pinfunction "3_3") (pintype "passive+no_connect"))
    )
    (net (code "95") (name "unconnected-(J9-Pad4)") (class "Default")
      (node (ref "J9") (pin "4") (pinfunction "4_4") (pintype "passive+no_connect"))
    )
    (net (code "96") (name "unconnected-(J9-Pad5)") (class "Default")
      (node (ref "J9") (pin "5") (pinfunction "5_5") (pintype "passive+no_connect"))
    )
    (net (code "97") (name "unconnected-(J10-Pad1)") (class "Default")
      (node (ref "J10") (pin "1") (pinfunction "1_1") (pintype "passive+no_connect"))
    )
    (net (code "98") (name "unconnected-(J10-Pad2)") (class "Default")
      (node (ref "J10") (pin "2") (pinfunction "2_2") (pintype "passive+no_connect"))
    )
    (net (code "99") (name "unconnected-(J10-Pad3)") (class "Default")
      (node (ref "J10") (pin "3") (pinfunction "3_3") (pintype "passive+no_connect"))
    )
    (net (code "100") (name "unconnected-(J10-Pad4)") (class "Default")
      (node (ref "J10") (pin "4") (pinfunction "4_4") (pintype "passive+no_connect"))
    )
    (net (code "101") (name "unconnected-(J10-Pad5)") (class "Default")
      (node (ref "J10") (pin "5") (pinfunction "5_5") (pintype "passive+no_connect"))
    )
    (net (code "102") (name "unconnected-(J11-Pad1)") (class "Default")
      (node (ref "J11") (pin "1") (pinfunction "1_1") (pintype "passive+no_connect"))
    )
    (net (code "103") (name "unconnected-(J11-Pad2)") (class "Default")
      (node (ref "J11") (pin "2") (pinfunction "2_2") (pintype "passive+no_connect"))
    )
    (net (code "104") (name "unconnected-(J11-Pad3)") (class "Default")
      (node (ref "J11") (pin "3") (pinfunction "3_3") (pintype "passive+no_connect"))
    )
    (net (code "105") (name "unconnected-(J11-Pad4)") (class "Default")
      (node (ref "J11") (pin "4") (pinfunction "4_4") (pintype "passive+no_connect"))
    )
    (net (code "106") (name "unconnected-(J11-Pad5)") (class "Default")
      (node (ref "J11") (pin "5") (pinfunction "5_5") (pintype "passive+no_connect"))
    )
    (net (code "107") (name "unconnected-(J15-Pad1)") (class "Default")
      (node (ref "J15") (pin "1") (pinfunction "1_1") (pintype "passive+no_connect"))
    )
    (net (code "108") (name "unconnected-(J15-Pad6)") (class "Default")
      (node (ref "J15") (pin "6") (pinfunction "6_6") (pintype "passive+no_connect"))
    )
    (net (code "109") (name "unconnected-(J16-Pad1)") (class "Default")
      (node (ref "J16") (pin "1") (pinfunction "1_1") (pintype "passive+no_connect"))
    )
    (net (code "110") (name "unconnected-(J16-Pad6)") (class "Default")
      (node (ref "J16") (pin "6") (pinfunction "6_6") (pintype "passive+no_connect"))
    )
    (net (code "111") (name "unconnected-(J17-Pad1)") (class "Default")
      (node (ref "J17") (pin "1") (pinfunction "1_1") (pintype "passive+no_connect"))
    )
    (net (code "112") (name "unconnected-(J17-Pad6)") (class "Default")
      (node (ref "J17") (pin "6") (pinfunction "6_6") (pintype "passive+no_connect"))
    )
    (net (code "113") (name "unconnected-(U1-VOUT-Pad4)") (class "Default")
      (node (ref "U1") (pin "4") (pinfunction "VOUT_4") (pintype "passive+no_connect"))
    )
  )
)
